# 608_donkey_030000.net
KiCad netlist of a schematic drawn in EAGLE
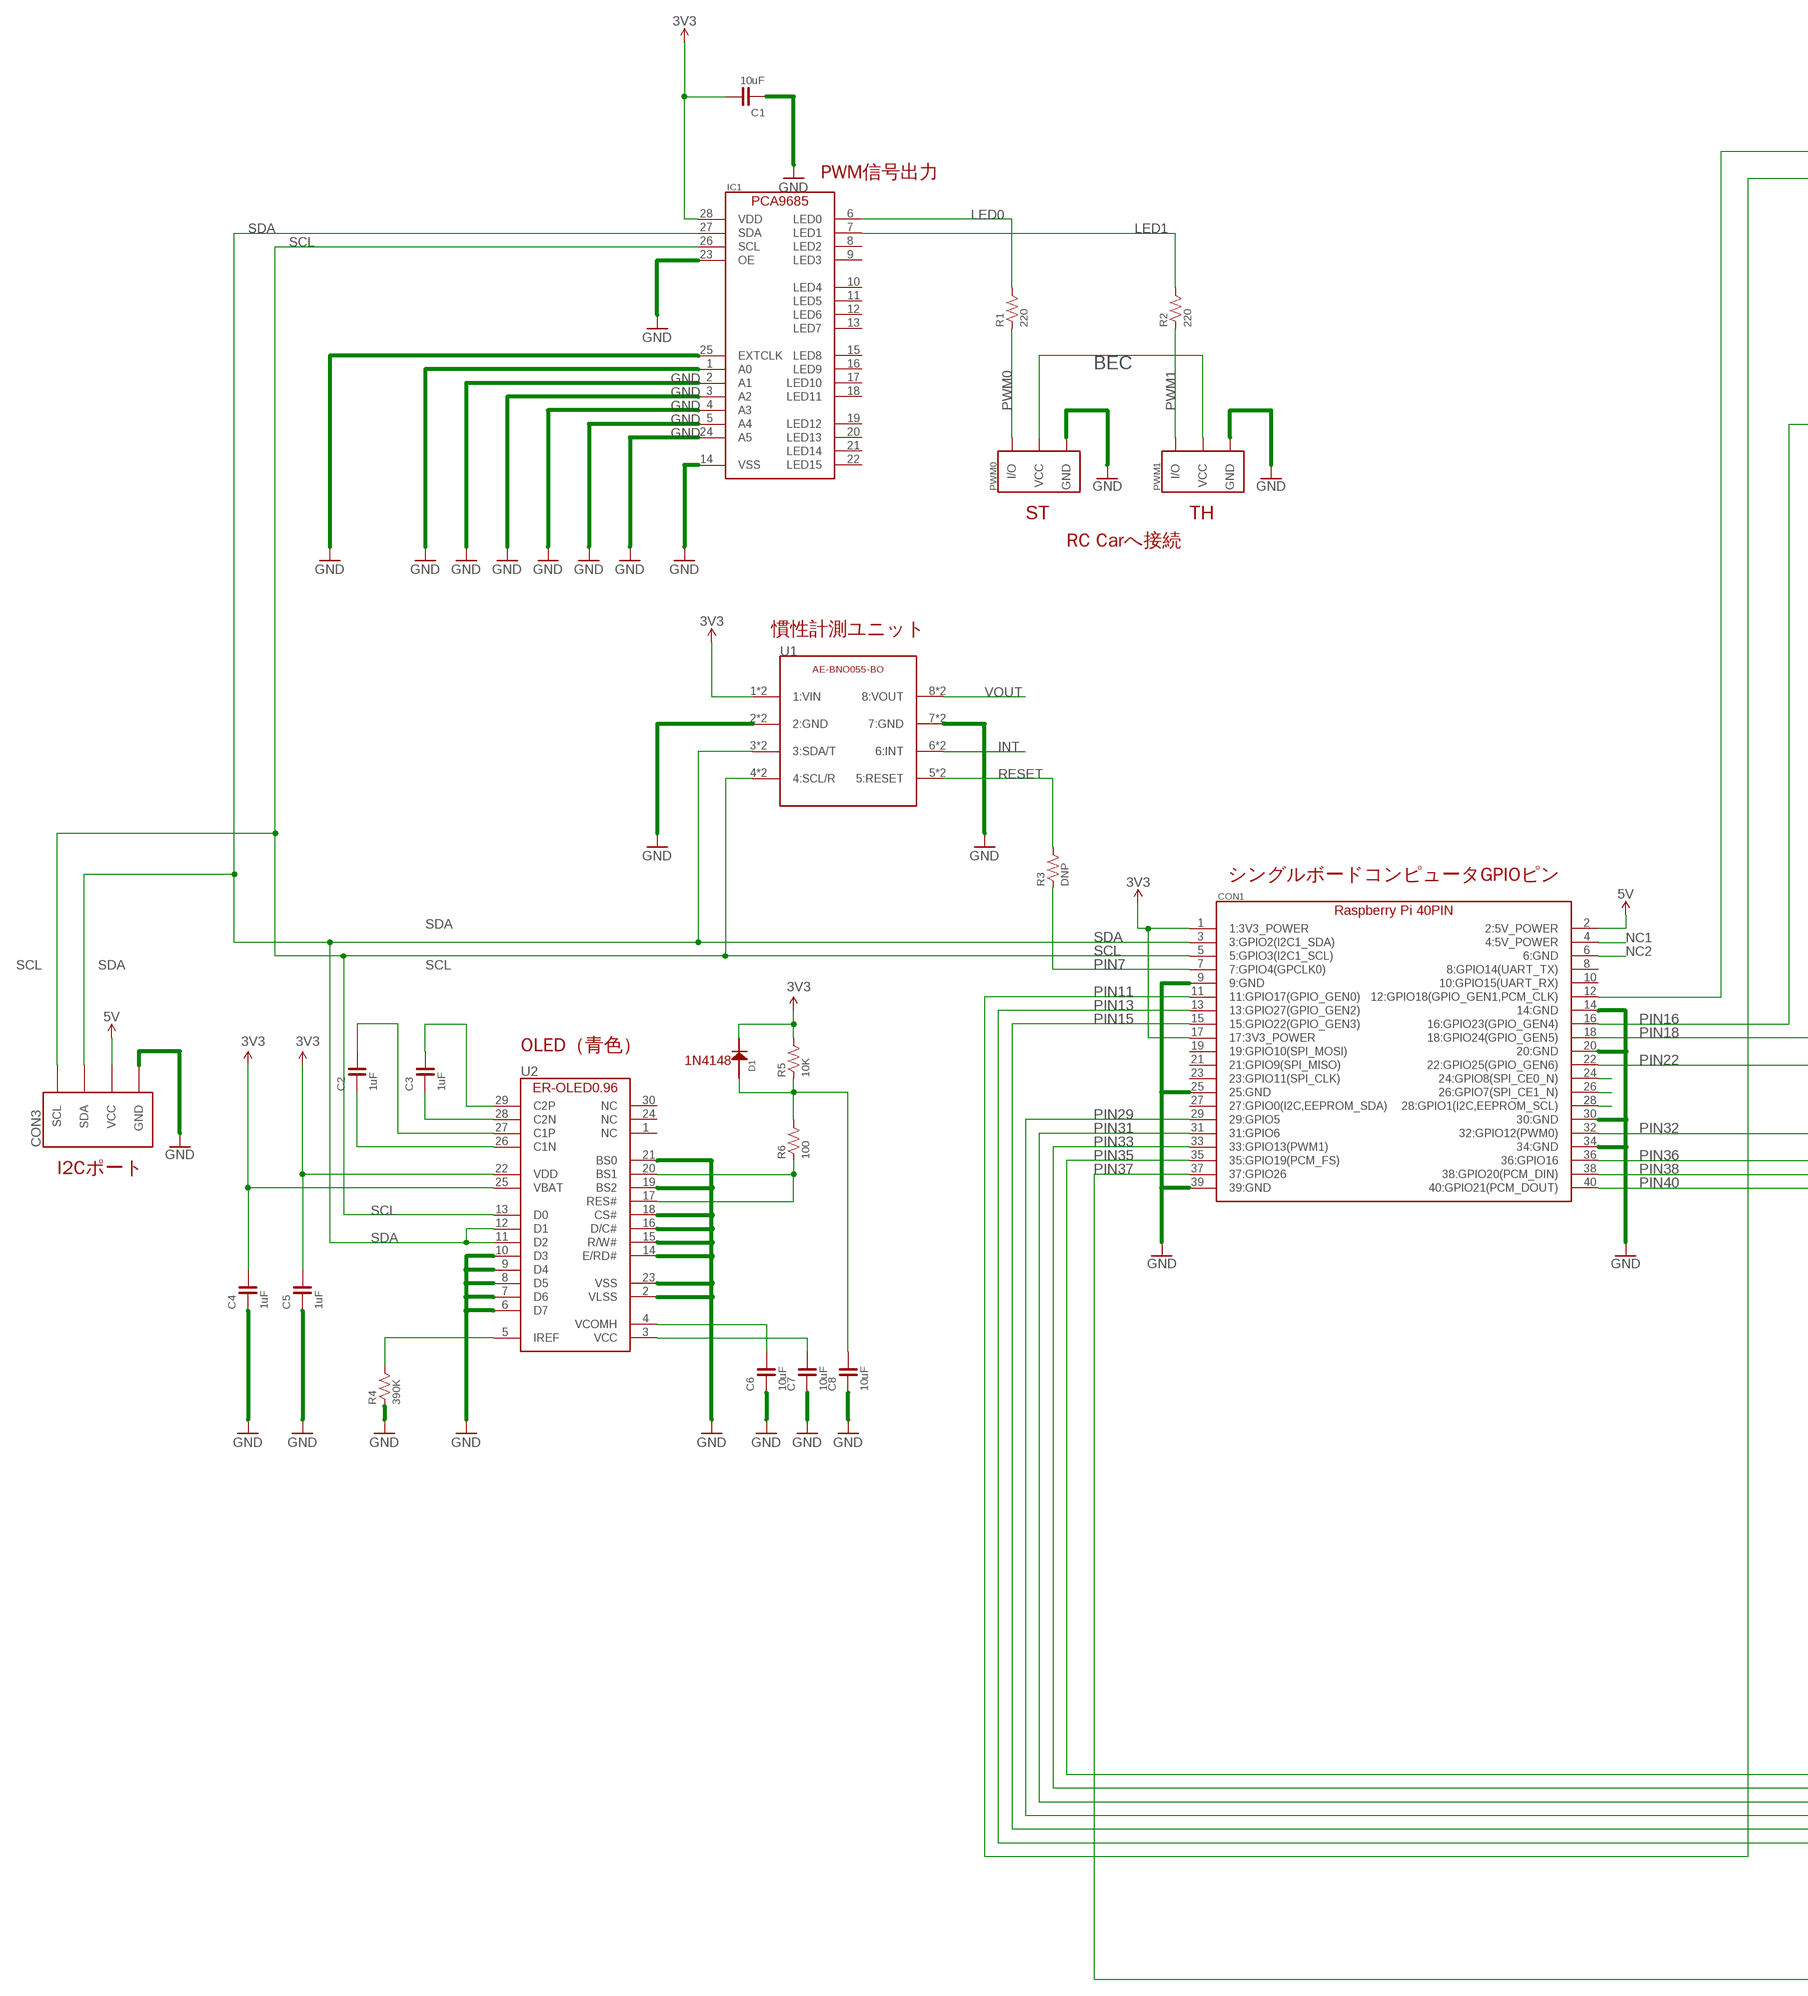
[diagram p0: schematic, sheet 1, part 1 of 3]
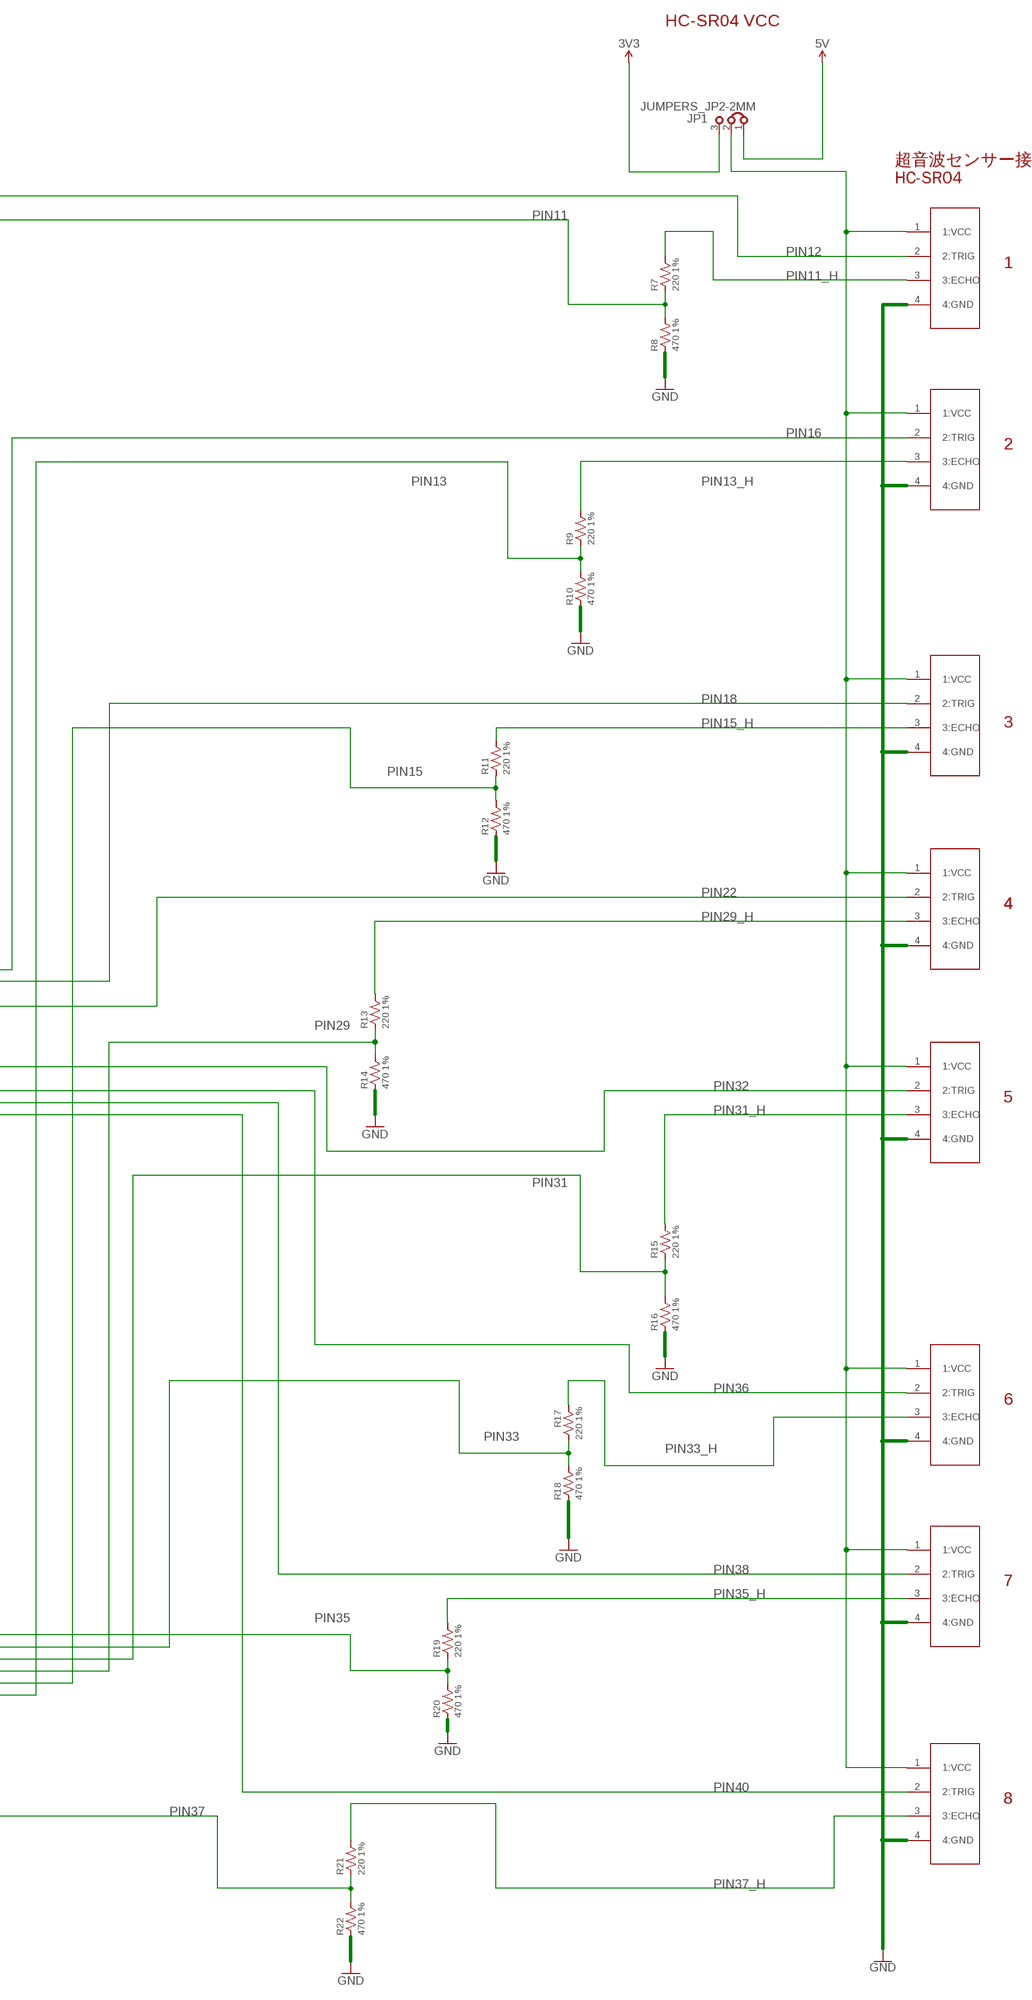
[diagram p1: schematic, sheet 1, part 2 of 3]
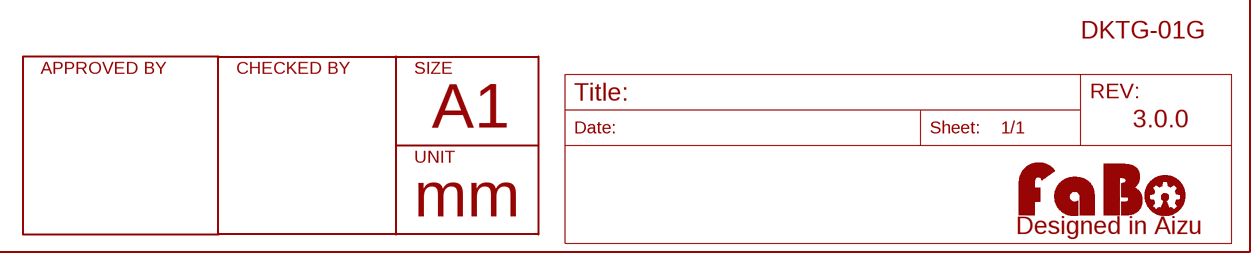
[diagram p2: schematic, sheet 1, part 3 of 3]

(export (version "E")
  (design (tool "Eeschema 10.0.6"))
  (components
    (comp (ref "C1")
      (value "10uF")
      (footprint "eagle-import:0603")
      (libsource (lib "eagle-import") (part "CAPACITOR-0603"))
    )
    (comp (ref "C2")
      (value "1uF")
      (footprint "eagle-import:0603-BOTTOM")
      (libsource (lib "eagle-import") (part "CAPACITOR-0603-BOTTOM"))
    )
    (comp (ref "C3")
      (value "1uF")
      (footprint "eagle-import:0603-BOTTOM")
      (libsource (lib "eagle-import") (part "CAPACITOR-0603-BOTTOM"))
    )
    (comp (ref "C4")
      (value "1uF")
      (footprint "eagle-import:0603-BOTTOM")
      (libsource (lib "eagle-import") (part "CAPACITOR-0603-BOTTOM"))
    )
    (comp (ref "C5")
      (value "1uF")
      (footprint "eagle-import:0603-BOTTOM")
      (libsource (lib "eagle-import") (part "CAPACITOR-0603-BOTTOM"))
    )
    (comp (ref "C6")
      (value "10uF")
      (footprint "eagle-import:0603-BOTTOM")
      (libsource (lib "eagle-import") (part "CAPACITOR-0603-BOTTOM"))
    )
    (comp (ref "C7")
      (value "10uF")
      (footprint "eagle-import:0603-BOTTOM")
      (libsource (lib "eagle-import") (part "CAPACITOR-0603-BOTTOM"))
    )
    (comp (ref "C8")
      (value "10uF")
      (footprint "eagle-import:0603-BOTTOM")
      (libsource (lib "eagle-import") (part "CAPACITOR-0603-BOTTOM"))
    )
    (comp (ref "CON1")
      (value "RASPBERRYPI_SHEILD")
      (footprint "eagle-import:RASPBERRY_PI_SHILED")
      (libsource (lib "eagle-import") (part "RASPBERRYPI_SHEILD"))
    )
    (comp (ref "CON3")
      (value "FABO_BRICK_I2C-S04B-PASK-2")
      (footprint "eagle-import:FABO_BRICK_I2C_S04B-PASK-2")
      (libsource (lib "eagle-import") (part "FABO_BRICK_I2C-S04B-PASK-2"))
    )
    (comp (ref "D1")
      (value "1N4148")
      (footprint "eagle-import:1N4148W")
      (libsource (lib "eagle-import") (part "1N4148"))
    )
    (comp (ref "HC1")
      (value "HC-SR04CONHS-SR04CON-SPEACING")
      (footprint "eagle-import:HC-SR04CON-SPEACE")
      (libsource (lib "eagle-import") (part "HC-SR04CONHS-SR04CON-SPEACING"))
    )
    (comp (ref "HC2")
      (value "HC-SR04CONHS-SR04CON-SPEACING")
      (footprint "eagle-import:HC-SR04CON-SPEACE")
      (libsource (lib "eagle-import") (part "HC-SR04CONHS-SR04CON-SPEACING"))
    )
    (comp (ref "HC3")
      (value "HC-SR04CONHS-SR04CON-SPEACING")
      (footprint "eagle-import:HC-SR04CON-SPEACE")
      (libsource (lib "eagle-import") (part "HC-SR04CONHS-SR04CON-SPEACING"))
    )
    (comp (ref "HC4")
      (value "HC-SR04CONHS-SR04CON-SPEACING")
      (footprint "eagle-import:HC-SR04CON-SPEACE")
      (libsource (lib "eagle-import") (part "HC-SR04CONHS-SR04CON-SPEACING"))
    )
    (comp (ref "HC5")
      (value "HC-SR04CONHS-SR04CON-SPEACING")
      (footprint "eagle-import:HC-SR04CON-SPEACE")
      (libsource (lib "eagle-import") (part "HC-SR04CONHS-SR04CON-SPEACING"))
    )
    (comp (ref "HC6")
      (value "HC-SR04CONHS-SR04CON-SPEACING")
      (footprint "eagle-import:HC-SR04CON-SPEACE")
      (libsource (lib "eagle-import") (part "HC-SR04CONHS-SR04CON-SPEACING"))
    )
    (comp (ref "HC7")
      (value "HC-SR04CONHS-SR04CON-SPEACING")
      (footprint "eagle-import:HC-SR04CON-SPEACE")
      (libsource (lib "eagle-import") (part "HC-SR04CONHS-SR04CON-SPEACING"))
    )
    (comp (ref "HC8")
      (value "HC-SR04CONHS-SR04CON-SPEACING")
      (footprint "eagle-import:HC-SR04CON-SPEACE")
      (libsource (lib "eagle-import") (part "HC-SR04CONHS-SR04CON-SPEACING"))
    )
    (comp (ref "IC1")
      (value "PCA9685BS")
      (footprint "eagle-import:PCA9685")
      (libsource (lib "eagle-import") (part "PCA9685BS"))
    )
    (comp (ref "JP1")
      (value "JUMPERS_JP2-2MM")
      (footprint "eagle-import:JUMPERS_JP2-2MM")
      (libsource (lib "eagle-import") (part "JUMPERS_JP2-2MM"))
    )
    (comp (ref "LOGO1")
      (value "LOGO_FABO-M")
      (footprint "eagle-import:LOGO_FABO_M")
      (libsource (lib "eagle-import") (part "LOGO_FABO-M"))
    )
    (comp (ref "PWM0")
      (value "PWM0")
      (footprint "eagle-import:PIN_1X3_NARROW")
      (libsource (lib "eagle-import") (part "FABO-BRICK-3PIN_HEADER"))
    )
    (comp (ref "PWM1")
      (value "PWM1")
      (footprint "eagle-import:PIN_1X3_NARROW")
      (libsource (lib "eagle-import") (part "FABO-BRICK-3PIN_HEADER"))
    )
    (comp (ref "R1")
      (value "220")
      (footprint "eagle-import:0603")
      (libsource (lib "eagle-import") (part "RESISTOR-0603"))
    )
    (comp (ref "R2")
      (value "220")
      (footprint "eagle-import:0603")
      (libsource (lib "eagle-import") (part "RESISTOR-0603"))
    )
    (comp (ref "R3")
      (value "DNP")
      (footprint "eagle-import:0603-BOTTOM")
      (libsource (lib "eagle-import") (part "RESISTOR-0603-BOTTOM"))
    )
    (comp (ref "R4")
      (value "390K")
      (footprint "eagle-import:0603-BOTTOM")
      (libsource (lib "eagle-import") (part "RESISTOR-0603-BOTTOM"))
    )
    (comp (ref "R5")
      (value "10K")
      (footprint "eagle-import:0603-BOTTOM")
      (libsource (lib "eagle-import") (part "RESISTOR-0603-BOTTOM"))
    )
    (comp (ref "R6")
      (value "100")
      (footprint "eagle-import:0603-BOTTOM")
      (libsource (lib "eagle-import") (part "RESISTOR-0603-BOTTOM"))
    )
    (comp (ref "R7")
      (value "220 1%")
      (footprint "eagle-import:0603")
      (libsource (lib "eagle-import") (part "RESISTOR-0603"))
    )
    (comp (ref "R8")
      (value "470 1%")
      (footprint "eagle-import:0603")
      (libsource (lib "eagle-import") (part "RESISTOR-0603"))
    )
    (comp (ref "R9")
      (value "220 1%")
      (footprint "eagle-import:0603")
      (libsource (lib "eagle-import") (part "RESISTOR-0603"))
    )
    (comp (ref "R10")
      (value "470 1%")
      (footprint "eagle-import:0603")
      (libsource (lib "eagle-import") (part "RESISTOR-0603"))
    )
    (comp (ref "R11")
      (value "220 1%")
      (footprint "eagle-import:0603")
      (libsource (lib "eagle-import") (part "RESISTOR-0603"))
    )
    (comp (ref "R12")
      (value "470 1%")
      (footprint "eagle-import:0603")
      (libsource (lib "eagle-import") (part "RESISTOR-0603"))
    )
    (comp (ref "R13")
      (value "220 1%")
      (footprint "eagle-import:0603")
      (libsource (lib "eagle-import") (part "RESISTOR-0603"))
    )
    (comp (ref "R14")
      (value "470 1%")
      (footprint "eagle-import:0603")
      (libsource (lib "eagle-import") (part "RESISTOR-0603"))
    )
    (comp (ref "R15")
      (value "220 1%")
      (footprint "eagle-import:0603")
      (libsource (lib "eagle-import") (part "RESISTOR-0603"))
    )
    (comp (ref "R16")
      (value "470 1%")
      (footprint "eagle-import:0603")
      (libsource (lib "eagle-import") (part "RESISTOR-0603"))
    )
    (comp (ref "R17")
      (value "220 1%")
      (footprint "eagle-import:0603")
      (libsource (lib "eagle-import") (part "RESISTOR-0603"))
    )
    (comp (ref "R18")
      (value "470 1%")
      (footprint "eagle-import:0603")
      (libsource (lib "eagle-import") (part "RESISTOR-0603"))
    )
    (comp (ref "R19")
      (value "220 1%")
      (footprint "eagle-import:0603")
      (libsource (lib "eagle-import") (part "RESISTOR-0603"))
    )
    (comp (ref "R20")
      (value "470 1%")
      (footprint "eagle-import:0603")
      (libsource (lib "eagle-import") (part "RESISTOR-0603"))
    )
    (comp (ref "R21")
      (value "220 1%")
      (footprint "eagle-import:0603")
      (libsource (lib "eagle-import") (part "RESISTOR-0603"))
    )
    (comp (ref "R22")
      (value "470 1%")
      (footprint "eagle-import:0603")
      (libsource (lib "eagle-import") (part "RESISTOR-0603"))
    )
    (comp (ref "U1")
      (value "AE-BNO055-BO")
      (footprint "eagle-import:DIP_8")
      (libsource (lib "eagle-import") (part "AE-BNO055-BO"))
    )
    (comp (ref "U2")
      (value "ER-OLED0.96-1ER-CON30HT-1_REV2")
      (footprint "eagle-import:ER-CON30HT-1_REV2")
      (libsource (lib "eagle-import") (part "ER-OLED0.96-1ER-CON30HT-1_REV2"))
    )
  )
  (nets
    (net (code "1") (name "/BEC") (class "Default")
      (node (ref "PWM0") (pin "2") (pinfunction "VCC_2") (pintype "bidirectional"))
      (node (ref "PWM1") (pin "2") (pinfunction "VCC_2") (pintype "bidirectional"))
    )
    (net (code "2") (name "/INT") (class "Default")
      (node (ref "U1") (pin "6") (pinfunction "6:INT_6") (pintype "output"))
      (node (ref "U1") (pin "6-1") (pinfunction "6:INT_6-1") (pintype "output"))
    )
    (net (code "3") (name "/LED0") (class "Default")
      (node (ref "IC1") (pin "6") (pinfunction "LED0_6") (pintype "bidirectional"))
      (node (ref "R1") (pin "2") (pinfunction "2_2") (pintype "bidirectional"))
    )
    (net (code "4") (name "/LED1") (class "Default")
      (node (ref "IC1") (pin "7") (pinfunction "LED1_7") (pintype "bidirectional"))
      (node (ref "R2") (pin "2") (pinfunction "2_2") (pintype "bidirectional"))
    )
    (net (code "5") (name "/NC1") (class "Default")
      (node (ref "CON1") (pin "4") (pinfunction "4:5V_POWER_4") (pintype "power_in"))
    )
    (net (code "6") (name "/NC2") (class "Default")
      (node (ref "CON1") (pin "6") (pinfunction "6:GND_6") (pintype "power_in"))
    )
    (net (code "7") (name "/PIN7") (class "Default")
      (node (ref "CON1") (pin "7") (pinfunction "7:GPIO4(GPCLK0)_7") (pintype "bidirectional"))
      (node (ref "R3") (pin "1") (pinfunction "1_1") (pintype "bidirectional"))
    )
    (net (code "8") (name "/PIN11") (class "Default")
      (node (ref "CON1") (pin "11") (pinfunction "11:GPIO17(GPIO_GEN0)_11") (pintype "bidirectional"))
      (node (ref "R7") (pin "1") (pinfunction "1_1") (pintype "bidirectional"))
      (node (ref "R8") (pin "2") (pinfunction "2_2") (pintype "bidirectional"))
    )
    (net (code "9") (name "/PIN11_H") (class "Default")
      (node (ref "HC1") (pin "3") (pinfunction "3:ECHO_3") (pintype "bidirectional"))
      (node (ref "R7") (pin "2") (pinfunction "2_2") (pintype "bidirectional"))
    )
    (net (code "10") (name "/PIN12") (class "Default")
      (node (ref "CON1") (pin "12") (pinfunction "12:GPIO18(GPIO_GEN1,PCM_CLK)_12") (pintype "bidirectional"))
      (node (ref "HC1") (pin "2") (pinfunction "2:TRIG_2") (pintype "bidirectional"))
    )
    (net (code "11") (name "/PIN13") (class "Default")
      (node (ref "CON1") (pin "13") (pinfunction "13:GPIO27(GPIO_GEN2)_13") (pintype "bidirectional"))
      (node (ref "R10") (pin "2") (pinfunction "2_2") (pintype "bidirectional"))
      (node (ref "R9") (pin "1") (pinfunction "1_1") (pintype "bidirectional"))
    )
    (net (code "12") (name "/PIN13_H") (class "Default")
      (node (ref "HC2") (pin "3") (pinfunction "3:ECHO_3") (pintype "bidirectional"))
      (node (ref "R9") (pin "2") (pinfunction "2_2") (pintype "bidirectional"))
    )
    (net (code "13") (name "/PIN15") (class "Default")
      (node (ref "CON1") (pin "15") (pinfunction "15:GPIO22(GPIO_GEN3)_15") (pintype "bidirectional"))
      (node (ref "R11") (pin "1") (pinfunction "1_1") (pintype "bidirectional"))
      (node (ref "R12") (pin "2") (pinfunction "2_2") (pintype "bidirectional"))
    )
    (net (code "14") (name "/PIN15_H") (class "Default")
      (node (ref "HC3") (pin "3") (pinfunction "3:ECHO_3") (pintype "bidirectional"))
      (node (ref "R11") (pin "2") (pinfunction "2_2") (pintype "bidirectional"))
    )
    (net (code "15") (name "/PIN16") (class "Default")
      (node (ref "CON1") (pin "16") (pinfunction "16:GPIO23(GPIO_GEN4)_16") (pintype "bidirectional"))
      (node (ref "HC2") (pin "2") (pinfunction "2:TRIG_2") (pintype "bidirectional"))
    )
    (net (code "16") (name "/PIN18") (class "Default")
      (node (ref "CON1") (pin "18") (pinfunction "18:GPIO24(GPIO_GEN5)_18") (pintype "bidirectional"))
      (node (ref "HC3") (pin "2") (pinfunction "2:TRIG_2") (pintype "bidirectional"))
    )
    (net (code "17") (name "/PIN22") (class "Default")
      (node (ref "CON1") (pin "22") (pinfunction "22:GPIO25(GPIO_GEN6)_22") (pintype "bidirectional"))
      (node (ref "HC4") (pin "2") (pinfunction "2:TRIG_2") (pintype "bidirectional"))
    )
    (net (code "18") (name "/PIN29") (class "Default")
      (node (ref "CON1") (pin "29") (pinfunction "29:GPIO5_29") (pintype "bidirectional"))
      (node (ref "R13") (pin "1") (pinfunction "1_1") (pintype "bidirectional"))
      (node (ref "R14") (pin "2") (pinfunction "2_2") (pintype "bidirectional"))
    )
    (net (code "19") (name "/PIN29_H") (class "Default")
      (node (ref "HC4") (pin "3") (pinfunction "3:ECHO_3") (pintype "bidirectional"))
      (node (ref "R13") (pin "2") (pinfunction "2_2") (pintype "bidirectional"))
    )
    (net (code "20") (name "/PIN31") (class "Default")
      (node (ref "CON1") (pin "31") (pinfunction "31:GPIO6_31") (pintype "bidirectional"))
      (node (ref "R15") (pin "1") (pinfunction "1_1") (pintype "bidirectional"))
      (node (ref "R16") (pin "2") (pinfunction "2_2") (pintype "bidirectional"))
    )
    (net (code "21") (name "/PIN31_H") (class "Default")
      (node (ref "HC5") (pin "3") (pinfunction "3:ECHO_3") (pintype "bidirectional"))
      (node (ref "R15") (pin "2") (pinfunction "2_2") (pintype "bidirectional"))
    )
    (net (code "22") (name "/PIN32") (class "Default")
      (node (ref "CON1") (pin "32") (pinfunction "32:GPIO12(PWM0)_32") (pintype "bidirectional"))
      (node (ref "HC5") (pin "2") (pinfunction "2:TRIG_2") (pintype "bidirectional"))
    )
    (net (code "23") (name "/PIN33") (class "Default")
      (node (ref "CON1") (pin "33") (pinfunction "33:GPIO13(PWM1)_33") (pintype "bidirectional"))
      (node (ref "R17") (pin "1") (pinfunction "1_1") (pintype "bidirectional"))
      (node (ref "R18") (pin "2") (pinfunction "2_2") (pintype "bidirectional"))
    )
    (net (code "24") (name "/PIN33_H") (class "Default")
      (node (ref "HC6") (pin "3") (pinfunction "3:ECHO_3") (pintype "bidirectional"))
      (node (ref "R17") (pin "2") (pinfunction "2_2") (pintype "bidirectional"))
    )
    (net (code "25") (name "/PIN35") (class "Default")
      (node (ref "CON1") (pin "35") (pinfunction "35:GPIO19(PCM_FS)_35") (pintype "bidirectional"))
      (node (ref "R19") (pin "1") (pinfunction "1_1") (pintype "bidirectional"))
      (node (ref "R20") (pin "2") (pinfunction "2_2") (pintype "bidirectional"))
    )
    (net (code "26") (name "/PIN35_H") (class "Default")
      (node (ref "HC7") (pin "3") (pinfunction "3:ECHO_3") (pintype "bidirectional"))
      (node (ref "R19") (pin "2") (pinfunction "2_2") (pintype "bidirectional"))
    )
    (net (code "27") (name "/PIN36") (class "Default")
      (node (ref "CON1") (pin "36") (pinfunction "36:GPIO16_36") (pintype "bidirectional"))
      (node (ref "HC6") (pin "2") (pinfunction "2:TRIG_2") (pintype "bidirectional"))
    )
    (net (code "28") (name "/PIN37") (class "Default")
      (node (ref "CON1") (pin "37") (pinfunction "37:GPIO26_37") (pintype "bidirectional"))
      (node (ref "R21") (pin "1") (pinfunction "1_1") (pintype "bidirectional"))
      (node (ref "R22") (pin "2") (pinfunction "2_2") (pintype "bidirectional"))
    )
    (net (code "29") (name "/PIN37_H") (class "Default")
      (node (ref "HC8") (pin "3") (pinfunction "3:ECHO_3") (pintype "bidirectional"))
      (node (ref "R21") (pin "2") (pinfunction "2_2") (pintype "bidirectional"))
    )
    (net (code "30") (name "/PIN38") (class "Default")
      (node (ref "CON1") (pin "38") (pinfunction "38:GPIO20(PCM_DIN)_38") (pintype "bidirectional"))
      (node (ref "HC7") (pin "2") (pinfunction "2:TRIG_2") (pintype "bidirectional"))
    )
    (net (code "31") (name "/PIN40") (class "Default")
      (node (ref "CON1") (pin "40") (pinfunction "40:GPIO21(PCM_DOUT)_40") (pintype "bidirectional"))
      (node (ref "HC8") (pin "2") (pinfunction "2:TRIG_2") (pintype "bidirectional"))
    )
    (net (code "32") (name "/PWM0") (class "Default")
      (node (ref "PWM0") (pin "1") (pinfunction "I/O_1") (pintype "bidirectional"))
      (node (ref "R1") (pin "1") (pinfunction "1_1") (pintype "bidirectional"))
    )
    (net (code "33") (name "/PWM1") (class "Default")
      (node (ref "PWM1") (pin "1") (pinfunction "I/O_1") (pintype "bidirectional"))
      (node (ref "R2") (pin "1") (pinfunction "1_1") (pintype "bidirectional"))
    )
    (net (code "34") (name "/RESET") (class "Default")
      (node (ref "R3") (pin "2") (pinfunction "2_2") (pintype "bidirectional"))
      (node (ref "U1") (pin "5") (pinfunction "5:RESET_5") (pintype "input"))
      (node (ref "U1") (pin "5-1") (pinfunction "5:RESET_5-1") (pintype "input"))
    )
    (net (code "35") (name "/SCL") (class "Default")
      (node (ref "CON1") (pin "5") (pinfunction "5:GPIO3(I2C1_SCL)_5") (pintype "bidirectional"))
      (node (ref "CON3") (pin "SCL") (pinfunction "SCL_SCL") (pintype "bidirectional"))
      (node (ref "IC1") (pin "26") (pinfunction "SCL_26") (pintype "bidirectional"))
      (node (ref "U1") (pin "4") (pinfunction "4:SCL/R_4") (pintype "bidirectional"))
      (node (ref "U1") (pin "4-1") (pinfunction "4:SCL/R_4-1") (pintype "bidirectional"))
      (node (ref "U2") (pin "13") (pinfunction "D0_13") (pintype "bidirectional"))
    )
    (net (code "36") (name "/SDA") (class "Default")
      (node (ref "CON1") (pin "3") (pinfunction "3:GPIO2(I2C1_SDA)_3") (pintype "bidirectional"))
      (node (ref "CON3") (pin "SDA") (pinfunction "SDA_SDA") (pintype "bidirectional"))
      (node (ref "IC1") (pin "27") (pinfunction "SDA_27") (pintype "bidirectional"))
      (node (ref "U1") (pin "3") (pinfunction "3:SDA/T_3") (pintype "bidirectional"))
      (node (ref "U1") (pin "3-1") (pinfunction "3:SDA/T_3-1") (pintype "bidirectional"))
      (node (ref "U2") (pin "11") (pinfunction "D2_11") (pintype "bidirectional"))
      (node (ref "U2") (pin "12") (pinfunction "D1_12") (pintype "bidirectional"))
    )
    (net (code "37") (name "/VOUT") (class "Default")
      (node (ref "U1") (pin "8") (pinfunction "8:VOUT_8") (pintype "power_in"))
      (node (ref "U1") (pin "8-1") (pinfunction "8:VOUT_8-1") (pintype "power_in"))
    )
    (net (code "38") (name "3V3") (class "Default")
      (node (ref "C1") (pin "2") (pinfunction "2_2") (pintype "passive"))
      (node (ref "C4") (pin "2") (pinfunction "2_2") (pintype "passive"))
      (node (ref "C5") (pin "2") (pinfunction "2_2") (pintype "passive"))
      (node (ref "CON1") (pin "1") (pinfunction "1:3V3_POWER_1") (pintype "power_in"))
      (node (ref "CON1") (pin "17") (pinfunction "17:3V3_POWER_17") (pintype "power_in"))
      (node (ref "D1") (pin "CATHODE") (pinfunction "CATHODE_CATHODE") (pintype "bidirectional"))
      (node (ref "IC1") (pin "28") (pinfunction "VDD_28") (pintype "bidirectional"))
      (node (ref "JP1") (pin "3") (pinfunction "3_3") (pintype "passive"))
      (node (ref "R5") (pin "2") (pinfunction "2_2") (pintype "bidirectional"))
      (node (ref "U1") (pin "1") (pinfunction "1:VIN_1") (pintype "power_in"))
      (node (ref "U1") (pin "1-1") (pinfunction "1:VIN_1-1") (pintype "power_in"))
      (node (ref "U2") (pin "22") (pinfunction "VDD_22") (pintype "bidirectional"))
      (node (ref "U2") (pin "25") (pinfunction "VBAT_25") (pintype "bidirectional"))
    )
    (net (code "39") (name "5V") (class "Default")
      (node (ref "CON1") (pin "2") (pinfunction "2:5V_POWER_2") (pintype "power_in"))
      (node (ref "CON3") (pin "VCC") (pinfunction "VCC_VCC") (pintype "bidirectional"))
      (node (ref "JP1") (pin "1") (pinfunction "1_1") (pintype "passive"))
    )
    (net (code "40") (name "GND") (class "Default")
      (node (ref "C1") (pin "1") (pinfunction "1_1") (pintype "passive"))
      (node (ref "C4") (pin "1") (pinfunction "1_1") (pintype "passive"))
      (node (ref "C5") (pin "1") (pinfunction "1_1") (pintype "passive"))
      (node (ref "C6") (pin "1") (pinfunction "1_1") (pintype "passive"))
      (node (ref "C7") (pin "1") (pinfunction "1_1") (pintype "passive"))
      (node (ref "C8") (pin "1") (pinfunction "1_1") (pintype "passive"))
      (node (ref "CON1") (pin "14") (pinfunction "14:GND_14") (pintype "power_in"))
      (node (ref "CON1") (pin "20") (pinfunction "20:GND_20") (pintype "power_in"))
      (node (ref "CON1") (pin "25") (pinfunction "25:GND_25") (pintype "power_in"))
      (node (ref "CON1") (pin "30") (pinfunction "30:GND_30") (pintype "power_in"))
      (node (ref "CON1") (pin "34") (pinfunction "34:GND_34") (pintype "power_in"))
      (node (ref "CON1") (pin "39") (pinfunction "39:GND_39") (pintype "power_in"))
      (node (ref "CON1") (pin "9") (pinfunction "9:GND_9") (pintype "power_in"))
      (node (ref "CON3") (pin "GND") (pinfunction "GND_GND") (pintype "bidirectional"))
      (node (ref "HC1") (pin "4") (pinfunction "4:GND_4") (pintype "bidirectional"))
      (node (ref "HC2") (pin "4") (pinfunction "4:GND_4") (pintype "bidirectional"))
      (node (ref "HC3") (pin "4") (pinfunction "4:GND_4") (pintype "bidirectional"))
      (node (ref "HC4") (pin "4") (pinfunction "4:GND_4") (pintype "bidirectional"))
      (node (ref "HC5") (pin "4") (pinfunction "4:GND_4") (pintype "bidirectional"))
      (node (ref "HC6") (pin "4") (pinfunction "4:GND_4") (pintype "bidirectional"))
      (node (ref "HC7") (pin "4") (pinfunction "4:GND_4") (pintype "bidirectional"))
      (node (ref "HC8") (pin "4") (pinfunction "4:GND_4") (pintype "bidirectional"))
      (node (ref "IC1") (pin "1") (pinfunction "A0_1") (pintype "bidirectional"))
      (node (ref "IC1") (pin "14") (pinfunction "VSS_14") (pintype "bidirectional"))
      (node (ref "IC1") (pin "2") (pinfunction "A1_2") (pintype "bidirectional"))
      (node (ref "IC1") (pin "23") (pinfunction "OE_23") (pintype "bidirectional"))
      (node (ref "IC1") (pin "24") (pinfunction "A5_24") (pintype "bidirectional"))
      (node (ref "IC1") (pin "25") (pinfunction "EXTCLK_25") (pintype "bidirectional"))
      (node (ref "IC1") (pin "3") (pinfunction "A2_3") (pintype "bidirectional"))
      (node (ref "IC1") (pin "4") (pinfunction "A3_4") (pintype "bidirectional"))
      (node (ref "IC1") (pin "5") (pinfunction "A4_5") (pintype "bidirectional"))
      (node (ref "PWM0") (pin "3") (pinfunction "GND_3") (pintype "bidirectional"))
      (node (ref "PWM1") (pin "3") (pinfunction "GND_3") (pintype "bidirectional"))
      (node (ref "R10") (pin "1") (pinfunction "1_1") (pintype "bidirectional"))
      (node (ref "R12") (pin "1") (pinfunction "1_1") (pintype "bidirectional"))
      (node (ref "R14") (pin "1") (pinfunction "1_1") (pintype "bidirectional"))
      (node (ref "R16") (pin "1") (pinfunction "1_1") (pintype "bidirectional"))
      (node (ref "R18") (pin "1") (pinfunction "1_1") (pintype "bidirectional"))
      (node (ref "R20") (pin "1") (pinfunction "1_1") (pintype "bidirectional"))
      (node (ref "R22") (pin "1") (pinfunction "1_1") (pintype "bidirectional"))
      (node (ref "R4") (pin "1") (pinfunction "1_1") (pintype "bidirectional"))
      (node (ref "R8") (pin "1") (pinfunction "1_1") (pintype "bidirectional"))
      (node (ref "U1") (pin "2") (pinfunction "2:GND_2") (pintype "power_in"))
      (node (ref "U1") (pin "2-1") (pinfunction "2:GND_2-1") (pintype "power_in"))
      (node (ref "U1") (pin "7") (pinfunction "7:GND_7") (pintype "power_in"))
      (node (ref "U1") (pin "7-1") (pinfunction "7:GND_7-1") (pintype "power_in"))
      (node (ref "U2") (pin "10") (pinfunction "D3_10") (pintype "bidirectional"))
      (node (ref "U2") (pin "14") (pinfunction "E/RD#_14") (pintype "bidirectional"))
      (node (ref "U2") (pin "15") (pinfunction "R/W#_15") (pintype "bidirectional"))
      (node (ref "U2") (pin "16") (pinfunction "D/C#_16") (pintype "bidirectional"))
      (node (ref "U2") (pin "18") (pinfunction "CS#_18") (pintype "bidirectional"))
      (node (ref "U2") (pin "19") (pinfunction "BS2_19") (pintype "bidirectional"))
      (node (ref "U2") (pin "2") (pinfunction "VLSS_2") (pintype "bidirectional"))
      (node (ref "U2") (pin "21") (pinfunction "BS0_21") (pintype "bidirectional"))
      (node (ref "U2") (pin "23") (pinfunction "VSS_23") (pintype "bidirectional"))
      (node (ref "U2") (pin "6") (pinfunction "D7_6") (pintype "bidirectional"))
      (node (ref "U2") (pin "7") (pinfunction "D6_7") (pintype "bidirectional"))
      (node (ref "U2") (pin "8") (pinfunction "D5_8") (pintype "bidirectional"))
      (node (ref "U2") (pin "9") (pinfunction "D4_9") (pintype "bidirectional"))
    )
    (net (code "41") (name "Net-(C8-Pad2)") (class "Default")
      (node (ref "C8") (pin "2") (pinfunction "2_2") (pintype "passive"))
      (node (ref "D1") (pin "ANODE") (pinfunction "ANODE_ANODE") (pintype "bidirectional"))
      (node (ref "R5") (pin "1") (pinfunction "1_1") (pintype "bidirectional"))
      (node (ref "R6") (pin "2") (pinfunction "2_2") (pintype "bidirectional"))
    )
    (net (code "42") (name "Net-(HC1-1:VCC)") (class "Default")
      (node (ref "HC1") (pin "1") (pinfunction "1:VCC_1") (pintype "bidirectional"))
      (node (ref "HC2") (pin "1") (pinfunction "1:VCC_1") (pintype "bidirectional"))
      (node (ref "HC3") (pin "1") (pinfunction "1:VCC_1") (pintype "bidirectional"))
      (node (ref "HC4") (pin "1") (pinfunction "1:VCC_1") (pintype "bidirectional"))
      (node (ref "HC5") (pin "1") (pinfunction "1:VCC_1") (pintype "bidirectional"))
      (node (ref "HC6") (pin "1") (pinfunction "1:VCC_1") (pintype "bidirectional"))
      (node (ref "HC7") (pin "1") (pinfunction "1:VCC_1") (pintype "bidirectional"))
      (node (ref "HC8") (pin "1") (pinfunction "1:VCC_1") (pintype "bidirectional"))
      (node (ref "JP1") (pin "2") (pinfunction "2_2") (pintype "passive"))
    )
    (net (code "43") (name "Net-(U2-BS1)") (class "Default")
      (node (ref "R6") (pin "1") (pinfunction "1_1") (pintype "bidirectional"))
      (node (ref "U2") (pin "17") (pinfunction "RES#_17") (pintype "bidirectional"))
      (node (ref "U2") (pin "20") (pinfunction "BS1_20") (pintype "bidirectional"))
    )
    (net (code "44") (name "Net-(U2-C1N)") (class "Default")
      (node (ref "C2") (pin "1") (pinfunction "1_1") (pintype "passive"))
      (node (ref "U2") (pin "26") (pinfunction "C1N_26") (pintype "bidirectional"))
    )
    (net (code "45") (name "Net-(U2-C1P)") (class "Default")
      (node (ref "C2") (pin "2") (pinfunction "2_2") (pintype "passive"))
      (node (ref "U2") (pin "27") (pinfunction "C1P_27") (pintype "bidirectional"))
    )
    (net (code "46") (name "Net-(U2-C2N)") (class "Default")
      (node (ref "C3") (pin "1") (pinfunction "1_1") (pintype "passive"))
      (node (ref "U2") (pin "28") (pinfunction "C2N_28") (pintype "bidirectional"))
    )
    (net (code "47") (name "Net-(U2-C2P)") (class "Default")
      (node (ref "C3") (pin "2") (pinfunction "2_2") (pintype "passive"))
      (node (ref "U2") (pin "29") (pinfunction "C2P_29") (pintype "bidirectional"))
    )
    (net (code "48") (name "Net-(U2-IREF)") (class "Default")
      (node (ref "R4") (pin "2") (pinfunction "2_2") (pintype "bidirectional"))
      (node (ref "U2") (pin "5") (pinfunction "IREF_5") (pintype "bidirectional"))
    )
    (net (code "49") (name "Net-(U2-VCC)") (class "Default")
      (node (ref "C7") (pin "2") (pinfunction "2_2") (pintype "passive"))
      (node (ref "U2") (pin "3") (pinfunction "VCC_3") (pintype "bidirectional"))
    )
    (net (code "50") (name "Net-(U2-VCOMH)") (class "Default")
      (node (ref "C6") (pin "2") (pinfunction "2_2") (pintype "passive"))
      (node (ref "U2") (pin "4") (pinfunction "VCOMH_4") (pintype "bidirectional"))
    )
    (net (code "51") (name "unconnected-(CON1-8:GPIO14(UART_TX)-Pad8)") (class "Default")
      (node (ref "CON1") (pin "8") (pinfunction "8:GPIO14(UART_TX)_8") (pintype "bidirectional"))
    )
    (net (code "52") (name "unconnected-(CON1-10:GPIO15(UART_RX)-Pad10)") (class "Default")
      (node (ref "CON1") (pin "10") (pinfunction "10:GPIO15(UART_RX)_10") (pintype "bidirectional"))
    )
    (net (code "53") (name "unconnected-(CON1-19:GPIO10(SPI_MOSI)-Pad19)") (class "Default")
      (node (ref "CON1") (pin "19") (pinfunction "19:GPIO10(SPI_MOSI)_19") (pintype "bidirectional"))
    )
    (net (code "54") (name "unconnected-(CON1-21:GPIO9(SPI_MISO)-Pad21)") (class "Default")
      (node (ref "CON1") (pin "21") (pinfunction "21:GPIO9(SPI_MISO)_21") (pintype "bidirectional"))
    )
    (net (code "55") (name "unconnected-(CON1-23:GPIO11(SPI_CLK)-Pad23)") (class "Default")
      (node (ref "CON1") (pin "23") (pinfunction "23:GPIO11(SPI_CLK)_23") (pintype "bidirectional"))
    )
    (net (code "56") (name "unconnected-(CON1-24:GPIO8(SPI_CE0_N)-Pad24)") (class "Default")
      (node (ref "CON1") (pin "24") (pinfunction "24:GPIO8(SPI_CE0_N)_24") (pintype "bidirectional"))
    )
    (net (code "57") (name "unconnected-(CON1-26:GPIO7(SPI_CE1_N)-Pad26)") (class "Default")
      (node (ref "CON1") (pin "26") (pinfunction "26:GPIO7(SPI_CE1_N)_26") (pintype "bidirectional"))
    )
    (net (code "58") (name "unconnected-(CON1-27:GPIO0(I2C,EEPROM_SDA)-Pad27)") (class "Default")
      (node (ref "CON1") (pin "27") (pinfunction "27:GPIO0(I2C,EEPROM_SDA)_27") (pintype "bidirectional"))
    )
    (net (code "59") (name "unconnected-(CON1-28:GPIO1(I2C,EEPROM_SCL)-Pad28)") (class "Default")
      (node (ref "CON1") (pin "28") (pinfunction "28:GPIO1(I2C,EEPROM_SCL)_28") (pintype "bidirectional"))
    )
    (net (code "60") (name "unconnected-(IC1-LED2-Pad8)") (class "Default")
      (node (ref "IC1") (pin "8") (pinfunction "LED2_8") (pintype "bidirectional"))
    )
    (net (code "61") (name "unconnected-(IC1-LED3-Pad9)") (class "Default")
      (node (ref "IC1") (pin "9") (pinfunction "LED3_9") (pintype "bidirectional"))
    )
    (net (code "62") (name "unconnected-(IC1-LED4-Pad10)") (class "Default")
      (node (ref "IC1") (pin "10") (pinfunction "LED4_10") (pintype "bidirectional"))
    )
    (net (code "63") (name "unconnected-(IC1-LED5-Pad11)") (class "Default")
      (node (ref "IC1") (pin "11") (pinfunction "LED5_11") (pintype "bidirectional"))
    )
    (net (code "64") (name "unconnected-(IC1-LED6-Pad12)") (class "Default")
      (node (ref "IC1") (pin "12") (pinfunction "LED6_12") (pintype "bidirectional"))
    )
    (net (code "65") (name "unconnected-(IC1-LED7-Pad13)") (class "Default")
      (node (ref "IC1") (pin "13") (pinfunction "LED7_13") (pintype "bidirectional"))
    )
    (net (code "66") (name "unconnected-(IC1-LED8-Pad15)") (class "Default")
      (node (ref "IC1") (pin "15") (pinfunction "LED8_15") (pintype "bidirectional"))
    )
    (net (code "67") (name "unconnected-(IC1-LED9-Pad16)") (class "Default")
      (node (ref "IC1") (pin "16") (pinfunction "LED9_16") (pintype "bidirectional"))
    )
    (net (code "68") (name "unconnected-(IC1-LED10-Pad17)") (class "Default")
      (node (ref "IC1") (pin "17") (pinfunction "LED10_17") (pintype "bidirectional"))
    )
    (net (code "69") (name "unconnected-(IC1-LED11-Pad18)") (class "Default")
      (node (ref "IC1") (pin "18") (pinfunction "LED11_18") (pintype "bidirectional"))
    )
    (net (code "70") (name "unconnected-(IC1-LED12-Pad19)") (class "Default")
      (node (ref "IC1") (pin "19") (pinfunction "LED12_19") (pintype "bidirectional"))
    )
    (net (code "71") (name "unconnected-(IC1-LED13-Pad20)") (class "Default")
      (node (ref "IC1") (pin "20") (pinfunction "LED13_20") (pintype "bidirectional"))
    )
    (net (code "72") (name "unconnected-(IC1-LED14-Pad21)") (class "Default")
      (node (ref "IC1") (pin "21") (pinfunction "LED14_21") (pintype "bidirectional"))
    )
    (net (code "73") (name "unconnected-(IC1-LED15-Pad22)") (class "Default")
      (node (ref "IC1") (pin "22") (pinfunction "LED15_22") (pintype "bidirectional"))
    )
    (net (code "74") (name "unconnected-(U2-NC-Pad1)") (class "Default")
      (node (ref "U2") (pin "1") (pinfunction "NC_1") (pintype "bidirectional"))
    )
    (net (code "75") (name "unconnected-(U2-NC-Pad24)") (class "Default")
      (node (ref "U2") (pin "24") (pinfunction "NC_24") (pintype "bidirectional"))
    )
    (net (code "76") (name "unconnected-(U2-NC-Pad30)") (class "Default")
      (node (ref "U2") (pin "30") (pinfunction "NC_30") (pintype "bidirectional"))
    )
  )
)
